# 50_ExpansorIO.net
KiCad netlist of a schematic drawn in Altium Designer
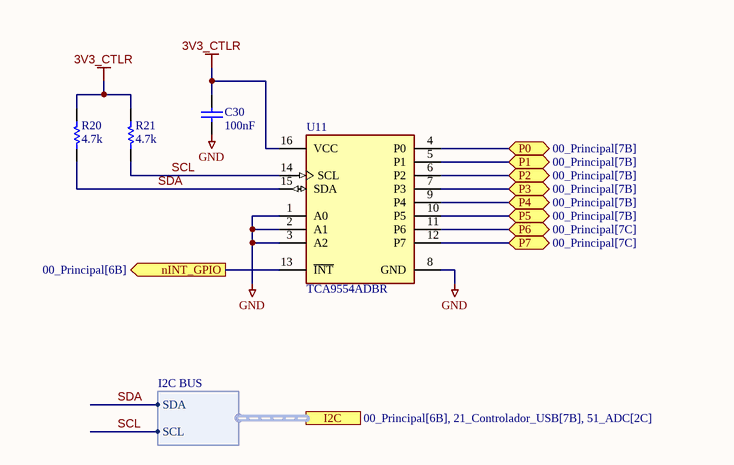
[diagram p0: 50_ExpansorIO.SchDoc]

(export (version "E")
  (design (tool "Eeschema 10.0.6"))
  (components
    (comp (ref "C30")
      (value "100nF")
      (footprint "CAPC1005X55X25NL05T05")
      (fields (field (name "MANUFACTURER") "Vitramon") (field (name "PART NUMBER") "VJ0402Y104KXJCW1BC"))
      (libsource (lib "Altium Content Vault") (part "CAP"))
    )
    (comp (ref "R20")
      (value "4.7k")
      (footprint "RESC1005X40X25ML05T10")
      (fields (field (name "MANUFACTURER") "Panasonic") (field (name "PART NUMBER") "ERJ-S02F4701X"))
      (libsource (lib "Altium Content Vault") (part "RES"))
    )
    (comp (ref "R21")
      (value "4.7k")
      (footprint "RESC1005X40X25ML05T10")
      (fields (field (name "MANUFACTURER") "Panasonic") (field (name "PART NUMBER") "ERJ-S02F4701X"))
      (libsource (lib "Altium Content Vault") (part "RES"))
    )
    (comp (ref "U11")
      (value "TCA9554ADBR")
      (footprint "FP-DB0016A-MFG")
      (description "IC SMBUS I/O EXPANDER I2C 16SSOP")
      (libsource (lib "Altium Content Vault") (part "5b8be9e160fc3a406f4826644c42a9b"))
    )
  )
  (nets
    (net (code "3") (name "/P0") (class "Default")
      (node (ref "U11") (pin "4") (pinfunction "P0_4") (pintype "passive"))
    )
    (net (code "4") (name "/P1") (class "Default")
      (node (ref "U11") (pin "5") (pinfunction "P1_5") (pintype "passive"))
    )
    (net (code "5") (name "/P2") (class "Default")
      (node (ref "U11") (pin "6") (pinfunction "P2_6") (pintype "passive"))
    )
    (net (code "6") (name "/P3") (class "Default")
      (node (ref "U11") (pin "7") (pinfunction "P3_7") (pintype "passive"))
    )
    (net (code "7") (name "/P4") (class "Default")
      (node (ref "U11") (pin "9") (pinfunction "P4_9") (pintype "passive"))
    )
    (net (code "8") (name "/P5") (class "Default")
      (node (ref "U11") (pin "10") (pinfunction "P5_10") (pintype "passive"))
    )
    (net (code "9") (name "/P6") (class "Default")
      (node (ref "U11") (pin "11") (pinfunction "P6_11") (pintype "passive"))
    )
    (net (code "10") (name "/P7") (class "Default")
      (node (ref "U11") (pin "12") (pinfunction "P7_12") (pintype "passive"))
    )
    (net (code "11") (name "/SCL") (class "Default")
      (node (ref "R21") (pin "1") (pinfunction "1_1") (pintype "passive"))
      (node (ref "U11") (pin "14") (pinfunction "SCL_14") (pintype "input"))
    )
    (net (code "12") (name "/SDA") (class "Default")
      (node (ref "R20") (pin "1") (pinfunction "1_1") (pintype "passive"))
      (node (ref "U11") (pin "15") (pinfunction "SDA_15") (pintype "bidirectional"))
    )
    (net (code "13") (name "/nINT_GPIO") (class "Default")
      (node (ref "U11") (pin "13") (pinfunction "~{INT}_13") (pintype "open_collector"))
    )
    (net (code "15") (name "3V3_CTLR") (class "Default")
      (node (ref "C30") (pin "2") (pinfunction "2_2") (pintype "passive"))
      (node (ref "R20") (pin "2") (pinfunction "2_2") (pintype "passive"))
      (node (ref "R21") (pin "2") (pinfunction "2_2") (pintype "passive"))
      (node (ref "U11") (pin "16") (pinfunction "VCC_16") (pintype "passive"))
    )
    (net (code "16") (name "GND") (class "Default")
      (node (ref "C30") (pin "1") (pinfunction "1_1") (pintype "passive"))
      (node (ref "U11") (pin "1") (pinfunction "A0_1") (pintype "passive"))
      (node (ref "U11") (pin "2") (pinfunction "A1_2") (pintype "passive"))
      (node (ref "U11") (pin "3") (pinfunction "A2_3") (pintype "passive"))
      (node (ref "U11") (pin "8") (pinfunction "GND_8") (pintype "passive"))
    )
  )
)
